# Sheet1.net
KiCad netlist of a schematic drawn in Altium Designer
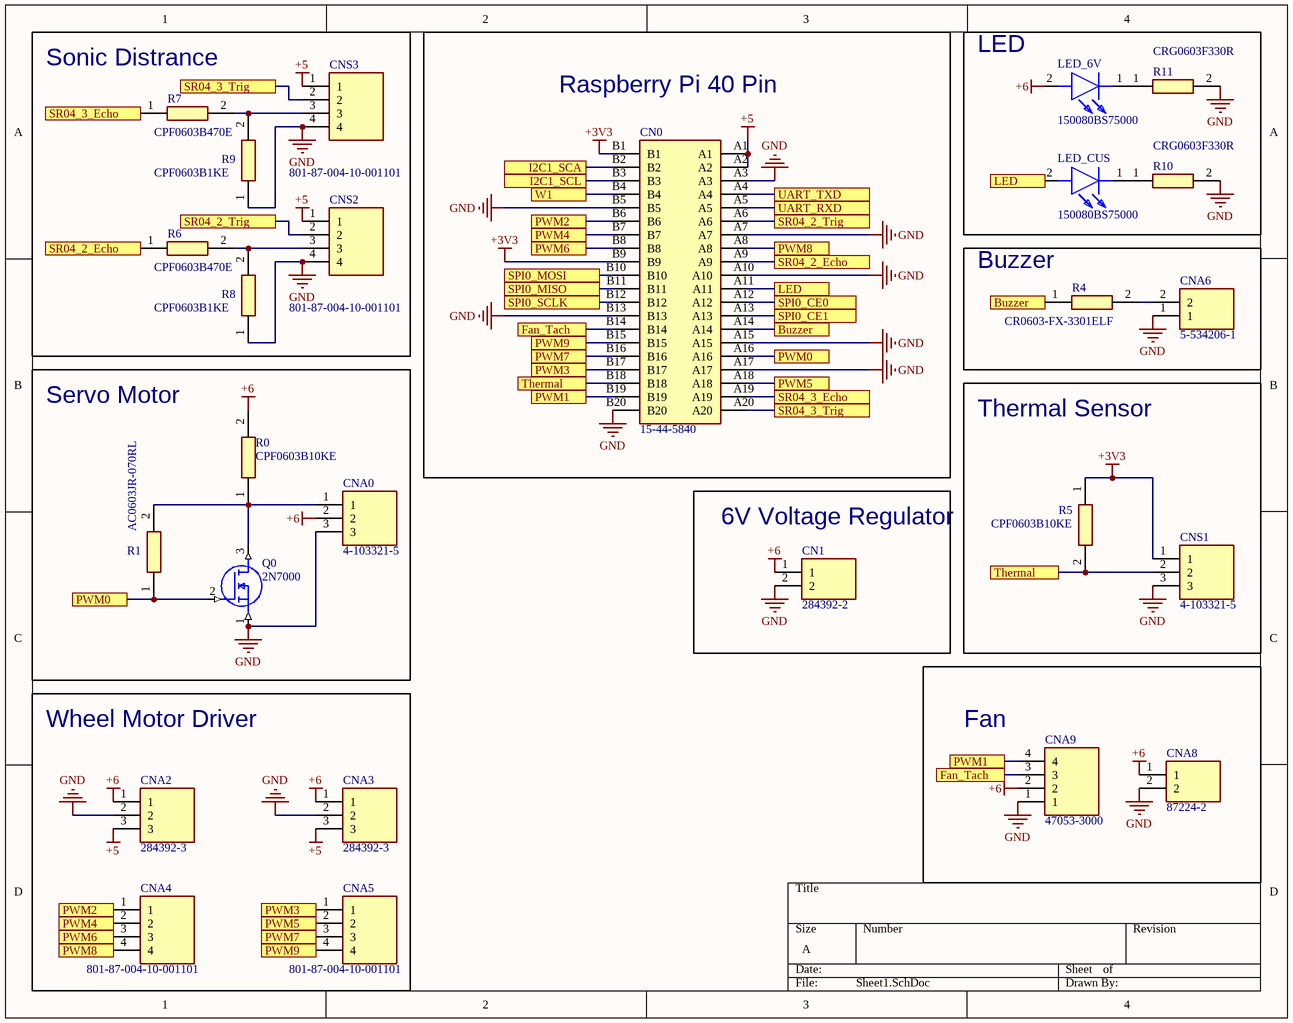
[diagram p0: Sheet1.SchDoc]

(export (version "E")
  (design (tool "Eeschema 10.0.6"))
  (components
    (comp (ref "CN0")
      (value "15-44-5840")
      (footprint "SamacSys:15445840")
      (description "Connector")
      (fields (field (name "MOUSER PART NUMBER") "538-15-44-5840"))
      (libsource (lib "*") (part "15-44-5840"))
    )
    (comp (ref "CN1")
      (value "284392-2")
      (footprint "SamacSys:2843922")
      (description "Connector")
      (fields (field (name "MOUSER PART NUMBER") "571-284392-2"))
      (libsource (lib "*") (part "284392-2"))
    )
    (comp (ref "CNA0")
      (value "4-103321-5")
      (footprint "SamacSys:HDRV3W69P0X254_1X3_721X234X1036P")
      (description "Connector")
      (fields (field (name "MOUSER PART NUMBER") "571-4-103321-5"))
      (libsource (lib "*") (part "4-103321-5"))
    )
    (comp (ref "CNA2")
      (value "284392-3")
      (footprint "SamacSys:2843923")
      (description "Connector")
      (fields (field (name "MOUSER PART NUMBER") "571-284392-3"))
      (libsource (lib "*") (part "284392-3"))
    )
    (comp (ref "CNA3")
      (value "284392-3")
      (footprint "SamacSys:2843923")
      (description "Connector")
      (fields (field (name "MOUSER PART NUMBER") "571-284392-3"))
      (libsource (lib "*") (part "284392-3"))
    )
    (comp (ref "CNA4")
      (value "801-87-004-10-001101")
      (footprint "SamacSys:RHDR4W60P0X254_1X4_1016X254X700P")
      (description "Connector")
      (fields (field (name "MOUSER PART NUMBER") "437-8018700410001101"))
      (libsource (lib "*") (part "801-87-004-10-001101"))
    )
    (comp (ref "CNA5")
      (value "801-87-004-10-001101")
      (footprint "SamacSys:RHDR4W60P0X254_1X4_1016X254X700P")
      (description "Connector")
      (fields (field (name "MOUSER PART NUMBER") "437-8018700410001101"))
      (libsource (lib "*") (part "801-87-004-10-001101"))
    )
    (comp (ref "CNA6")
      (value "5-534206-1")
      (footprint "SamacSys:55342061")
      (description "Connector")
      (fields (field (name "MOUSER PART NUMBER") "571-5-534206-1"))
      (libsource (lib "*") (part "5-534206-1"))
    )
    (comp (ref "CNA8")
      (value "87224-2")
      (footprint "SamacSys:872242")
      (description "Connector")
      (fields (field (name "MOUSER PART NUMBER") "571-872242"))
      (libsource (lib "*") (part "87224-2"))
    )
    (comp (ref "CNA9")
      (value "47053-3000")
      (footprint "SamacSys:470533000")
      (description "Connector")
      (fields (field (name "MOUSER PART NUMBER") "538-47053-3000"))
      (libsource (lib "*") (part "47053-3000"))
    )
    (comp (ref "CNS1")
      (value "4-103321-5")
      (footprint "SamacSys:HDRV3W69P0X254_1X3_721X234X1036P")
      (description "Connector")
      (fields (field (name "MOUSER PART NUMBER") "571-4-103321-5"))
      (libsource (lib "*") (part "4-103321-5"))
    )
    (comp (ref "CNS2")
      (value "801-87-004-10-001101")
      (footprint "SamacSys:RHDR4W60P0X254_1X4_1016X254X700P")
      (description "Connector")
      (fields (field (name "MOUSER PART NUMBER") "437-8018700410001101"))
      (libsource (lib "*") (part "801-87-004-10-001101"))
    )
    (comp (ref "CNS3")
      (value "801-87-004-10-001101")
      (footprint "SamacSys:RHDR4W60P0X254_1X4_1016X254X700P")
      (description "Connector")
      (fields (field (name "MOUSER PART NUMBER") "437-8018700410001101"))
      (libsource (lib "*") (part "801-87-004-10-001101"))
    )
    (comp (ref "LED_6V")
      (value "150080BS75000")
      (footprint "SamacSys:LEDC2012X80N")
      (description "LED")
      (fields (field (name "MOUSER PART NUMBER") "710-150080BS75000"))
      (libsource (lib "*") (part "150080BS75000"))
    )
    (comp (ref "LED_CUS")
      (value "150080BS75000")
      (footprint "SamacSys:LEDC2012X80N")
      (description "LED")
      (fields (field (name "MOUSER PART NUMBER") "710-150080BS75000"))
      (libsource (lib "*") (part "150080BS75000"))
    )
    (comp (ref "Q0")
      (value "2N7000")
      (footprint "SamacSys:TO-92_(TO-226)")
      (description "MOSFET (N-Channel)")
      (fields (field (name "MOUSER PART NUMBER") "512-2N7000"))
      (libsource (lib "*") (part "2N7000"))
    )
    (comp (ref "R0")
      (value "CPF0603B10KE")
      (footprint "SamacSys:RESC1608X55N")
      (description "Resistor")
      (fields (field (name "MOUSER PART NUMBER") "279-CPF0603B10KE"))
      (libsource (lib "*") (part "CPF0603B10KE"))
    )
    (comp (ref "R1")
      (value "AC0603JR-070RL")
      (footprint "SamacSys:RESC1608X55N")
      (description "Resistor")
      (fields (field (name "MOUSER PART NUMBER") "603-AC0603JR-070RL"))
      (libsource (lib "*") (part "AC0603JR-070RL"))
    )
    (comp (ref "R4")
      (value "CR0603-FX-3301ELF")
      (footprint "SamacSys:RESC1608X55N")
      (description "Resistor")
      (fields (field (name "MOUSER PART NUMBER") "652-CR0603-FX3301ELF"))
      (libsource (lib "*") (part "CR0603-FX-3301ELF"))
    )
    (comp (ref "R5")
      (value "CPF0603B10KE")
      (footprint "SamacSys:RESC1608X55N")
      (description "Resistor")
      (fields (field (name "MOUSER PART NUMBER") "279-CPF0603B10KE"))
      (libsource (lib "") (part "CPF0603B10KE_1"))
    )
    (comp (ref "R6")
      (value "CPF0603B470E")
      (footprint "SamacSys:RESC1608X55N")
      (description "Resistor")
      (fields
        (field (name "MANUFACTURER_PART_NUMBER") "CPF0603B470KE")
        (field (name "MOUSER PART NUMBER") "279-CPF0603B470KE")
      )
      (libsource (lib "*") (part "CPF0603B470KE"))
    )
    (comp (ref "R7")
      (value "CPF0603B470E")
      (footprint "SamacSys:RESC1608X55N")
      (description "Resistor")
      (fields
        (field (name "MANUFACTURER_PART_NUMBER") "CPF0603B470KE")
        (field (name "MOUSER PART NUMBER") "279-CPF0603B470KE")
      )
      (libsource (lib "*") (part "CPF0603B470KE"))
    )
    (comp (ref "R8")
      (value "CPF0603B1KE")
      (footprint "SamacSys:RESC1608X55N")
      (description "Resistor")
      (fields
        (field (name "MANUFACTURER_PART_NUMBER") "CPF0603B10RE1")
        (field (name "MOUSER PART NUMBER") "279-CPF0603B10RE1")
      )
      (libsource (lib "*") (part "CPF0603B10RE1"))
    )
    (comp (ref "R9")
      (value "CPF0603B1KE")
      (footprint "SamacSys:RESC1608X55N")
      (description "Resistor")
      (fields
        (field (name "MANUFACTURER_PART_NUMBER") "CPF0603B10RE1")
        (field (name "MOUSER PART NUMBER") "279-CPF0603B10RE1")
      )
      (libsource (lib "*") (part "CPF0603B10RE1"))
    )
    (comp (ref "R10")
      (value "CRG0603F330R")
      (footprint "SamacSys:RESC1608X55N")
      (description "Resistor")
      (fields (field (name "MOUSER PART NUMBER") "279-CRG0603F330R"))
      (libsource (lib "*") (part "CRG0603F330R"))
    )
    (comp (ref "R11")
      (value "CRG0603F330R")
      (footprint "SamacSys:RESC1608X55N")
      (description "Resistor")
      (fields (field (name "MOUSER PART NUMBER") "279-CRG0603F330R"))
      (libsource (lib "*") (part "CRG0603F330R"))
    )
  )
  (nets
    (net (code "1") (name "+3V3") (class "Default")
      (node (ref "CN0") (pin "B1") (pinfunction "B1_B1") (pintype "passive"))
      (node (ref "CN0") (pin "B9") (pinfunction "B9_B9") (pintype "passive"))
      (node (ref "CNS1") (pin "1") (pinfunction "1_1") (pintype "passive"))
      (node (ref "R5") (pin "1") (pinfunction "1_1") (pintype "passive"))
    )
    (net (code "2") (name "+5") (class "Default")
      (node (ref "CN0") (pin "A1") (pinfunction "A1_A1") (pintype "passive"))
      (node (ref "CN0") (pin "A2") (pinfunction "A2_A2") (pintype "passive"))
      (node (ref "CNA2") (pin "3") (pinfunction "3_3") (pintype "passive"))
      (node (ref "CNA3") (pin "3") (pinfunction "3_3") (pintype "passive"))
      (node (ref "CNS2") (pin "1") (pinfunction "1_1") (pintype "passive"))
      (node (ref "CNS3") (pin "1") (pinfunction "1_1") (pintype "passive"))
    )
    (net (code "3") (name "+6") (class "Default")
      (node (ref "CN1") (pin "1") (pinfunction "1_1") (pintype "passive"))
      (node (ref "CNA0") (pin "2") (pinfunction "2_2") (pintype "passive"))
      (node (ref "CNA2") (pin "1") (pinfunction "1_1") (pintype "passive"))
      (node (ref "CNA3") (pin "1") (pinfunction "1_1") (pintype "passive"))
      (node (ref "CNA8") (pin "1") (pinfunction "1_1") (pintype "passive"))
      (node (ref "CNA9") (pin "2") (pinfunction "2_2") (pintype "passive"))
      (node (ref "LED_6V") (pin "2") (pinfunction "A_2") (pintype "passive"))
      (node (ref "R0") (pin "2") (pinfunction "2_2") (pintype "passive"))
    )
    (net (code "4") (name "/Buzzer") (class "Default")
      (node (ref "CN0") (pin "A14") (pinfunction "A14_A14") (pintype "passive"))
      (node (ref "R4") (pin "1") (pinfunction "1_1") (pintype "passive"))
    )
    (net (code "5") (name "/Fan_Tach") (class "Default")
      (node (ref "CN0") (pin "B14") (pinfunction "B14_B14") (pintype "passive"))
      (node (ref "CNA9") (pin "3") (pinfunction "3_3") (pintype "passive"))
    )
    (net (code "6") (name "/I2C1_SCA") (class "Default")
      (node (ref "CN0") (pin "B2") (pinfunction "B2_B2") (pintype "passive"))
    )
    (net (code "7") (name "/I2C1_SCL") (class "Default")
      (node (ref "CN0") (pin "B3") (pinfunction "B3_B3") (pintype "passive"))
    )
    (net (code "8") (name "/LED") (class "Default")
      (node (ref "CN0") (pin "A11") (pinfunction "A11_A11") (pintype "passive"))
      (node (ref "LED_CUS") (pin "2") (pinfunction "A_2") (pintype "passive"))
    )
    (net (code "9") (name "/PWM0") (class "Default")
      (node (ref "CN0") (pin "A16") (pinfunction "A16_A16") (pintype "passive"))
      (node (ref "Q0") (pin "2") (pinfunction "G_2") (pintype "input"))
      (node (ref "R1") (pin "1") (pinfunction "1_1") (pintype "passive"))
    )
    (net (code "10") (name "/PWM1") (class "Default")
      (node (ref "CN0") (pin "B19") (pinfunction "B19_B19") (pintype "passive"))
      (node (ref "CNA9") (pin "4") (pinfunction "4_4") (pintype "passive"))
    )
    (net (code "11") (name "/PWM2") (class "Default")
      (node (ref "CN0") (pin "B6") (pinfunction "B6_B6") (pintype "passive"))
      (node (ref "CNA4") (pin "1") (pinfunction "1_1") (pintype "passive"))
    )
    (net (code "12") (name "/PWM3") (class "Default")
      (node (ref "CN0") (pin "B17") (pinfunction "B17_B17") (pintype "passive"))
      (node (ref "CNA5") (pin "1") (pinfunction "1_1") (pintype "passive"))
    )
    (net (code "13") (name "/PWM4") (class "Default")
      (node (ref "CN0") (pin "B7") (pinfunction "B7_B7") (pintype "passive"))
      (node (ref "CNA4") (pin "2") (pinfunction "2_2") (pintype "passive"))
    )
    (net (code "14") (name "/PWM5") (class "Default")
      (node (ref "CN0") (pin "A18") (pinfunction "A18_A18") (pintype "passive"))
      (node (ref "CNA5") (pin "2") (pinfunction "2_2") (pintype "passive"))
    )
    (net (code "15") (name "/PWM6") (class "Default")
      (node (ref "CN0") (pin "B8") (pinfunction "B8_B8") (pintype "passive"))
      (node (ref "CNA4") (pin "3") (pinfunction "3_3") (pintype "passive"))
    )
    (net (code "16") (name "/PWM7") (class "Default")
      (node (ref "CN0") (pin "B16") (pinfunction "B16_B16") (pintype "passive"))
      (node (ref "CNA5") (pin "3") (pinfunction "3_3") (pintype "passive"))
    )
    (net (code "17") (name "/PWM8") (class "Default")
      (node (ref "CN0") (pin "A8") (pinfunction "A8_A8") (pintype "passive"))
      (node (ref "CNA4") (pin "4") (pinfunction "4_4") (pintype "passive"))
    )
    (net (code "18") (name "/PWM9") (class "Default")
      (node (ref "CN0") (pin "B15") (pinfunction "B15_B15") (pintype "passive"))
      (node (ref "CNA5") (pin "4") (pinfunction "4_4") (pintype "passive"))
    )
    (net (code "19") (name "/SPI0_CE0") (class "Default")
      (node (ref "CN0") (pin "A12") (pinfunction "A12_A12") (pintype "passive"))
    )
    (net (code "20") (name "/SPI0_CE1") (class "Default")
      (node (ref "CN0") (pin "A13") (pinfunction "A13_A13") (pintype "passive"))
    )
    (net (code "21") (name "/SPI0_MISO") (class "Default")
      (node (ref "CN0") (pin "B11") (pinfunction "B11_B11") (pintype "passive"))
    )
    (net (code "22") (name "/SPI0_MOSI") (class "Default")
      (node (ref "CN0") (pin "B10") (pinfunction "B10_B10") (pintype "passive"))
    )
    (net (code "23") (name "/SPI0_SCLK") (class "Default")
      (node (ref "CN0") (pin "B12") (pinfunction "B12_B12") (pintype "passive"))
    )
    (net (code "24") (name "/SR04_2_Echo") (class "Default")
      (node (ref "CN0") (pin "A9") (pinfunction "A9_A9") (pintype "passive"))
      (node (ref "R6") (pin "1") (pinfunction "1_1") (pintype "passive"))
    )
    (net (code "25") (name "/SR04_2_Trig") (class "Default")
      (node (ref "CN0") (pin "A6") (pinfunction "A6_A6") (pintype "passive"))
      (node (ref "CNS2") (pin "2") (pinfunction "2_2") (pintype "passive"))
    )
    (net (code "26") (name "/SR04_3_Echo") (class "Default")
      (node (ref "CN0") (pin "A19") (pinfunction "A19_A19") (pintype "passive"))
      (node (ref "R7") (pin "1") (pinfunction "1_1") (pintype "passive"))
    )
    (net (code "27") (name "/SR04_3_Trig") (class "Default")
      (node (ref "CN0") (pin "A20") (pinfunction "A20_A20") (pintype "passive"))
      (node (ref "CNS3") (pin "2") (pinfunction "2_2") (pintype "passive"))
    )
    (net (code "28") (name "/Thermal") (class "Default")
      (node (ref "CN0") (pin "B18") (pinfunction "B18_B18") (pintype "passive"))
      (node (ref "CNS1") (pin "2") (pinfunction "2_2") (pintype "passive"))
      (node (ref "R5") (pin "2") (pinfunction "2_2") (pintype "passive"))
    )
    (net (code "29") (name "/UART_RXD") (class "Default")
      (node (ref "CN0") (pin "A5") (pinfunction "A5_A5") (pintype "passive"))
    )
    (net (code "30") (name "/UART_TXD") (class "Default")
      (node (ref "CN0") (pin "A4") (pinfunction "A4_A4") (pintype "passive"))
    )
    (net (code "31") (name "/W1") (class "Default")
      (node (ref "CN0") (pin "B4") (pinfunction "B4_B4") (pintype "passive"))
    )
    (net (code "32") (name "GND") (class "Default")
      (node (ref "CN0") (pin "A10") (pinfunction "A10_A10") (pintype "passive"))
      (node (ref "CN0") (pin "A15") (pinfunction "A15_A15") (pintype "passive"))
      (node (ref "CN0") (pin "A17") (pinfunction "A17_A17") (pintype "passive"))
      (node (ref "CN0") (pin "A3") (pinfunction "A3_A3") (pintype "passive"))
      (node (ref "CN0") (pin "A7") (pinfunction "A7_A7") (pintype "passive"))
      (node (ref "CN0") (pin "B13") (pinfunction "B13_B13") (pintype "passive"))
      (node (ref "CN0") (pin "B20") (pinfunction "B20_B20") (pintype "passive"))
      (node (ref "CN0") (pin "B5") (pinfunction "B5_B5") (pintype "passive"))
      (node (ref "CN1") (pin "2") (pinfunction "2_2") (pintype "passive"))
      (node (ref "CNA0") (pin "3") (pinfunction "3_3") (pintype "passive"))
      (node (ref "CNA2") (pin "2") (pinfunction "2_2") (pintype "passive"))
      (node (ref "CNA3") (pin "2") (pinfunction "2_2") (pintype "passive"))
      (node (ref "CNA6") (pin "1") (pinfunction "1_1") (pintype "passive"))
      (node (ref "CNA8") (pin "2") (pinfunction "2_2") (pintype "passive"))
      (node (ref "CNA9") (pin "1") (pinfunction "1_1") (pintype "passive"))
      (node (ref "CNS1") (pin "3") (pinfunction "3_3") (pintype "passive"))
      (node (ref "CNS2") (pin "4") (pinfunction "4_4") (pintype "passive"))
      (node (ref "CNS3") (pin "4") (pinfunction "4_4") (pintype "passive"))
      (node (ref "Q0") (pin "1") (pinfunction "S_1") (pintype "input"))
      (node (ref "R10") (pin "2") (pinfunction "2_2") (pintype "passive"))
      (node (ref "R11") (pin "2") (pinfunction "2_2") (pintype "passive"))
      (node (ref "R8") (pin "1") (pinfunction "1_1") (pintype "passive"))
      (node (ref "R9") (pin "1") (pinfunction "1_1") (pintype "passive"))
    )
    (net (code "33") (name "Net-(CNA6-Pad2)") (class "Default")
      (node (ref "CNA6") (pin "2") (pinfunction "2_2") (pintype "passive"))
      (node (ref "R4") (pin "2") (pinfunction "2_2") (pintype "passive"))
    )
    (net (code "34") (name "Net-(CNS2-Pad3)") (class "Default")
      (node (ref "CNS2") (pin "3") (pinfunction "3_3") (pintype "passive"))
      (node (ref "R6") (pin "2") (pinfunction "2_2") (pintype "passive"))
      (node (ref "R8") (pin "2") (pinfunction "2_2") (pintype "passive"))
    )
    (net (code "35") (name "Net-(CNS3-Pad3)") (class "Default")
      (node (ref "CNS3") (pin "3") (pinfunction "3_3") (pintype "passive"))
      (node (ref "R7") (pin "2") (pinfunction "2_2") (pintype "passive"))
      (node (ref "R9") (pin "2") (pinfunction "2_2") (pintype "passive"))
    )
    (net (code "36") (name "Net-(LED_6V-K)") (class "Default")
      (node (ref "LED_6V") (pin "1") (pinfunction "K_1") (pintype "passive"))
      (node (ref "R11") (pin "1") (pinfunction "1_1") (pintype "passive"))
    )
    (net (code "37") (name "Net-(LED_CUS-K)") (class "Default")
      (node (ref "LED_CUS") (pin "1") (pinfunction "K_1") (pintype "passive"))
      (node (ref "R10") (pin "1") (pinfunction "1_1") (pintype "passive"))
    )
    (net (code "38") (name "Net-(Q0-D)") (class "Default")
      (node (ref "CNA0") (pin "1") (pinfunction "1_1") (pintype "passive"))
      (node (ref "Q0") (pin "3") (pinfunction "D_3") (pintype "output"))
      (node (ref "R0") (pin "1") (pinfunction "1_1") (pintype "passive"))
      (node (ref "R1") (pin "2") (pinfunction "2_2") (pintype "passive"))
    )
  )
)
